# ProProject___2024-03-14.net
KiCad netlist of a schematic drawn in EasyEDA Pro
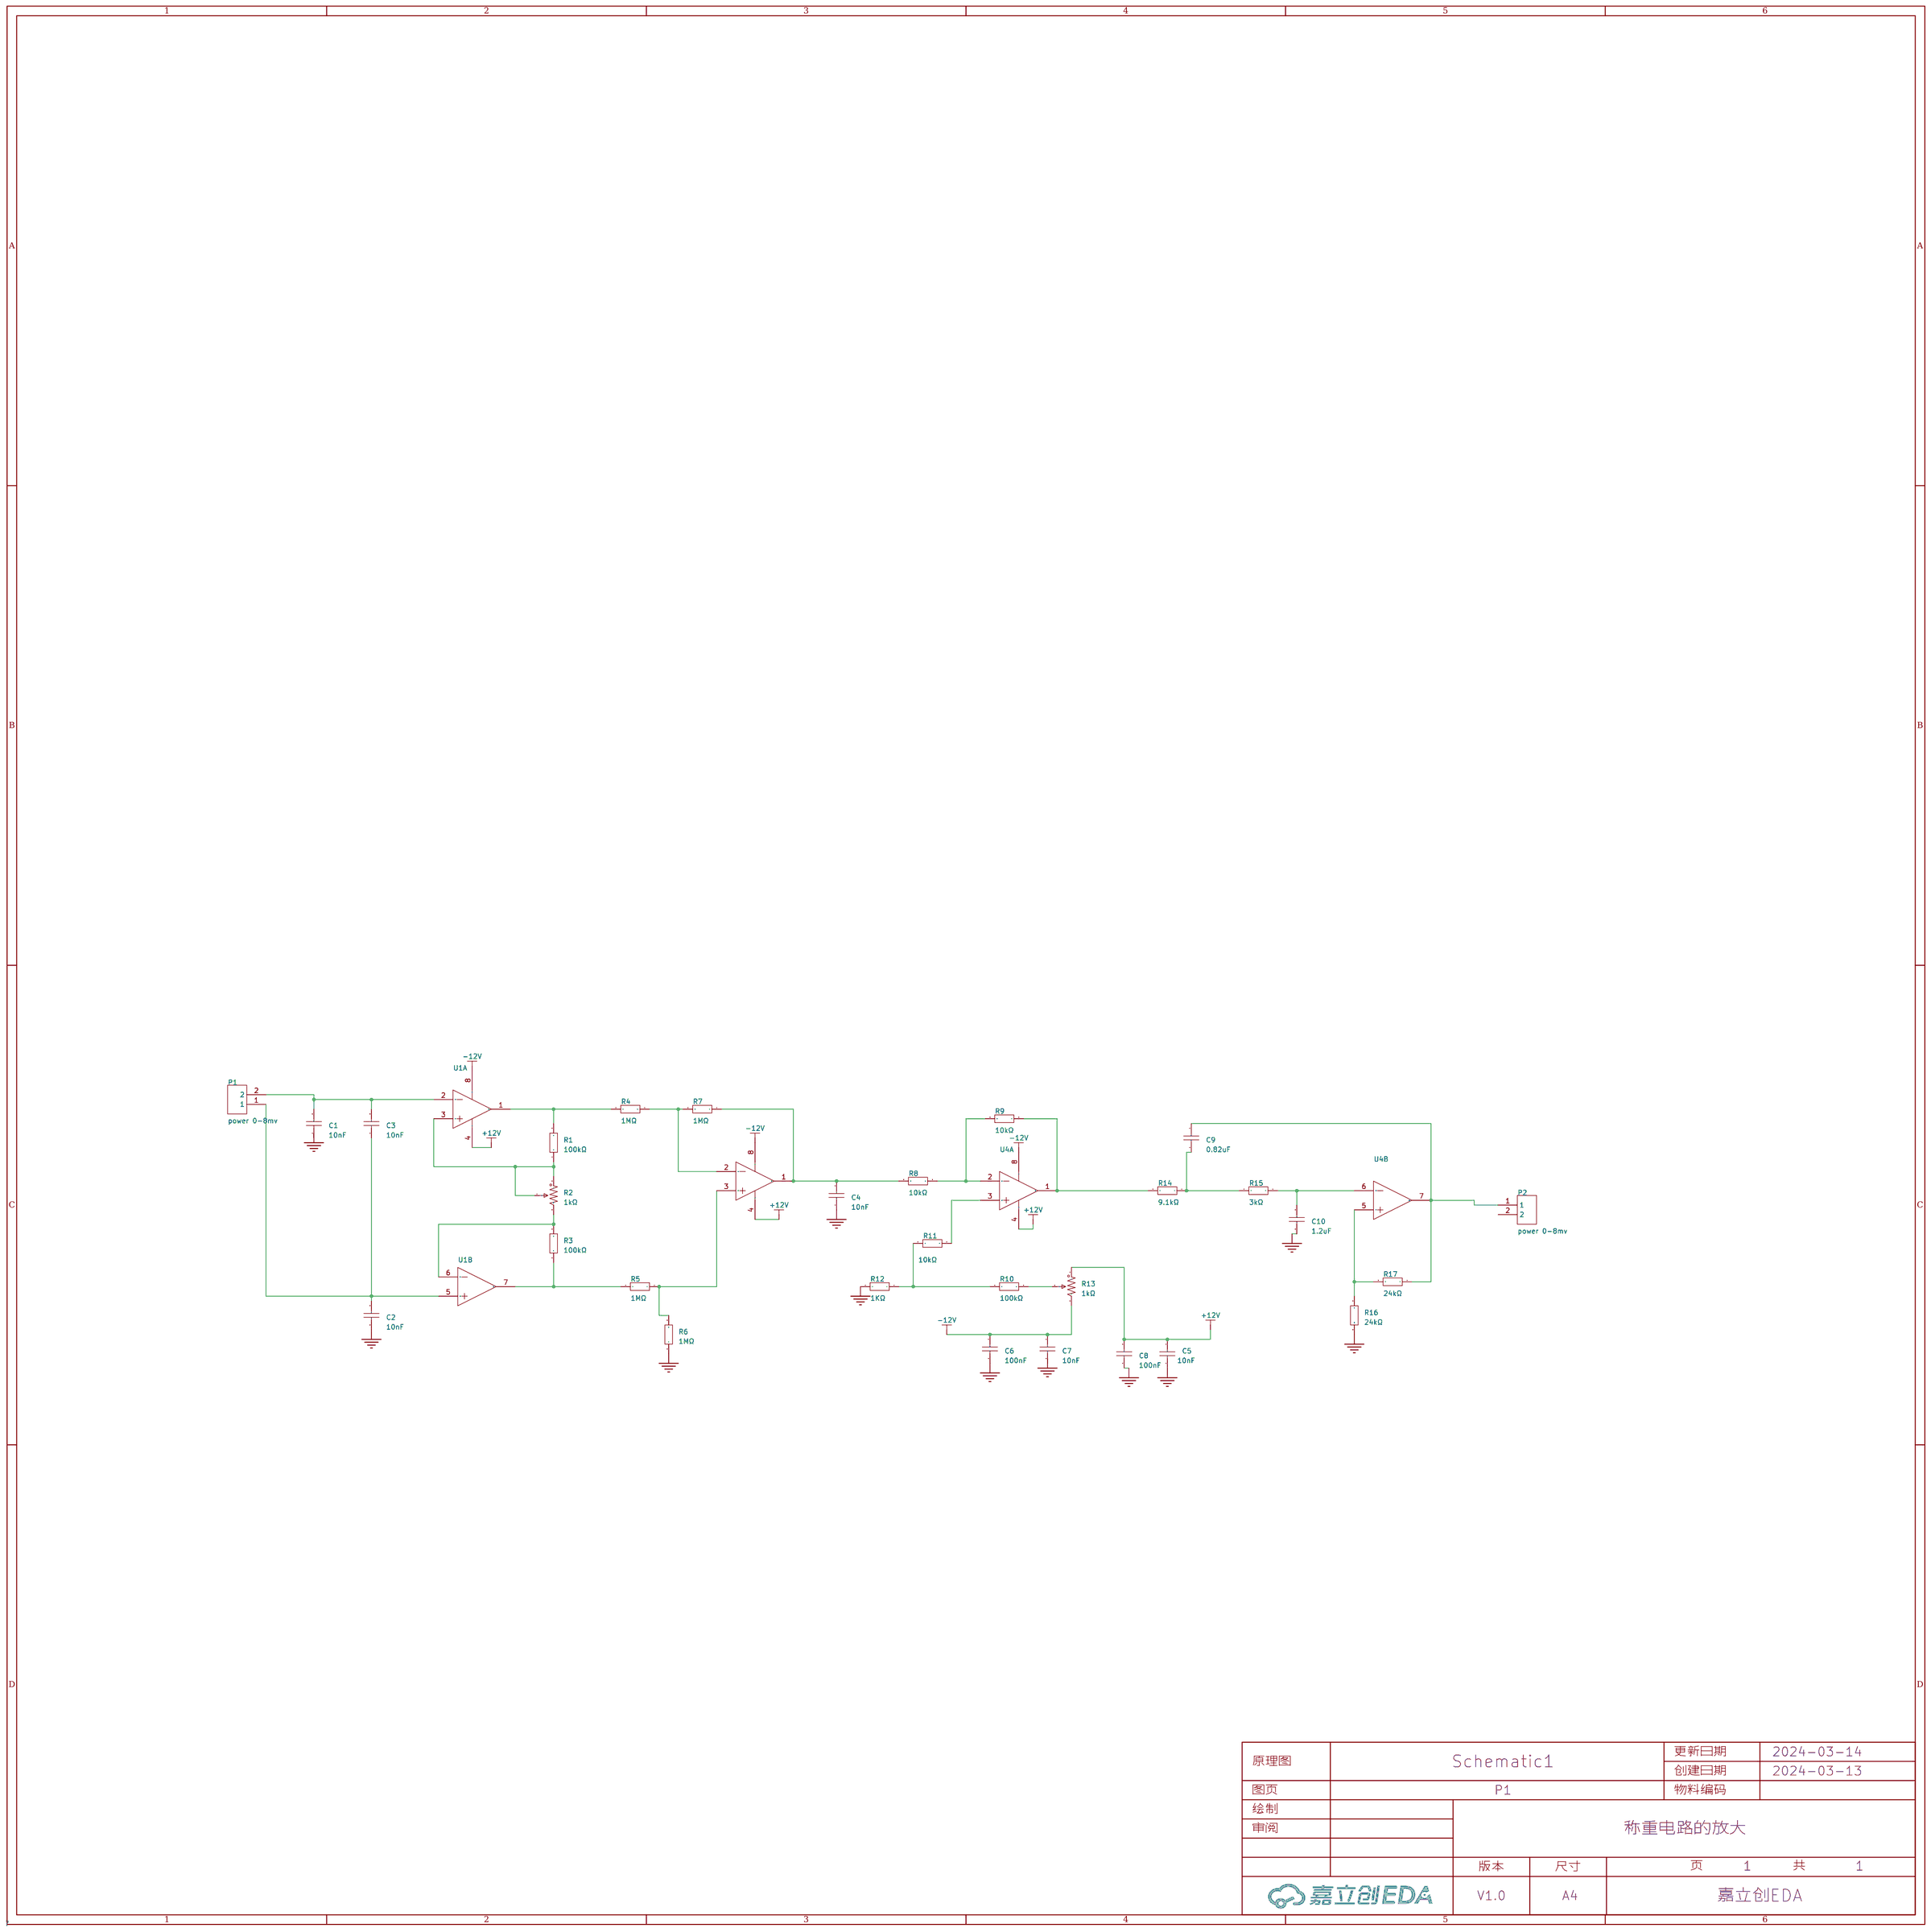
[diagram p0: schematic sheet]

(export (version "E")
  (design (tool "Eeschema 10.0.6"))
  (components
    (comp (ref "C1")
      (value "10nF")
      (footprint "easyedapro:C0603")
      (description "容值:100nF;精度:±10%;额定电压:50V;材质(温度系数):X7R;")
      (fields (field (name "Manufacturer Part") "0603B104K500NT") (field (name "Manufacturer") "FH(风华)"))
      (libsource (lib "easyedapro") (part "0603B104K500NT"))
    )
    (comp (ref "C2")
      (value "10nF")
      (footprint "easyedapro:C0603")
      (description "容值:100nF;精度:±10%;额定电压:50V;材质(温度系数):X7R;")
      (fields (field (name "Manufacturer Part") "0603B104K500NT") (field (name "Manufacturer") "FH(风华)"))
      (libsource (lib "easyedapro") (part "0603B104K500NT"))
    )
    (comp (ref "C3")
      (value "10nF")
      (footprint "easyedapro:C0603")
      (description "容值:100nF;精度:±10%;额定电压:50V;材质(温度系数):X7R;")
      (fields (field (name "Manufacturer Part") "0603B104K500NT") (field (name "Manufacturer") "FH(风华)"))
      (libsource (lib "easyedapro") (part "0603B104K500NT"))
    )
    (comp (ref "C4")
      (value "10nF")
      (footprint "easyedapro:C0603")
      (description "容值:100nF;精度:±10%;额定电压:50V;材质(温度系数):X7R;")
      (fields (field (name "Manufacturer Part") "0603B104K500NT") (field (name "Manufacturer") "FH(风华)"))
      (libsource (lib "easyedapro") (part "0603B104K500NT"))
    )
    (comp (ref "C5")
      (value "10nF")
      (footprint "easyedapro:C0603")
      (description "容值:100nF;精度:±10%;额定电压:50V;材质(温度系数):X7R;")
      (fields (field (name "Manufacturer Part") "0603B104K500NT") (field (name "Manufacturer") "FH(风华)"))
      (libsource (lib "easyedapro") (part "0603B104K500NT"))
    )
    (comp (ref "C6")
      (value "100nF")
      (footprint "easyedapro:C0603")
      (description "容值:100nF;精度:±10%;额定电压:50V;材质(温度系数):X7R;")
      (fields (field (name "Manufacturer Part") "0603B104K500NT") (field (name "Manufacturer") "FH(风华)"))
      (libsource (lib "easyedapro") (part "0603B104K500NT"))
    )
    (comp (ref "C7")
      (value "10nF")
      (footprint "easyedapro:C0603")
      (description "容值:100nF;精度:±10%;额定电压:50V;材质(温度系数):X7R;")
      (fields (field (name "Manufacturer Part") "0603B104K500NT") (field (name "Manufacturer") "FH(风华)"))
      (libsource (lib "easyedapro") (part "0603B104K500NT"))
    )
    (comp (ref "C8")
      (value "100nF")
      (footprint "easyedapro:C0603")
      (description "容值:100nF;精度:±10%;额定电压:50V;材质(温度系数):X7R;")
      (fields (field (name "Manufacturer Part") "0603B104K500NT") (field (name "Manufacturer") "FH(风华)"))
      (libsource (lib "easyedapro") (part "0603B104K500NT"))
    )
    (comp (ref "C9")
      (value "0.82uF")
      (footprint "easyedapro:C0603")
      (description "容值:100nF;精度:±10%;额定电压:50V;材质(温度系数):X7R;")
      (fields (field (name "Manufacturer Part") "0603B104K500NT") (field (name "Manufacturer") "FH(风华)"))
      (libsource (lib "easyedapro") (part "0603B104K500NT"))
    )
    (comp (ref "C10")
      (value "1.2uF")
      (footprint "easyedapro:C0603")
      (description "容值:100nF;精度:±10%;额定电压:50V;材质(温度系数):X7R;")
      (fields (field (name "Manufacturer Part") "0603B104K500NT") (field (name "Manufacturer") "FH(风华)"))
      (libsource (lib "easyedapro") (part "0603B104K500NT"))
    )
    (comp (ref "P1")
      (value "power 0-8mv")
      (footprint "easyedapro:CONN-TH_2P-P5.00_WJ500V-5.08-2P")
      (fields (field (name "Manufacturer") "KANGNEX(康奈克斯电气)"))
      (libsource (lib "easyedapro") (part "WJ500V-5.08-2P-14-00A"))
    )
    (comp (ref "P2")
      (value "power 0-8mv")
      (footprint "easyedapro:CONN-TH_2P-P5.00_WJ500V-5.08-2P")
      (fields (field (name "Manufacturer") "KANGNEX(康奈克斯电气)"))
      (libsource (lib "easyedapro") (part "WJ500V-5.08-2P-14-00A"))
    )
    (comp (ref "R1")
      (value "100kΩ")
      (footprint "easyedapro:R0603")
      (description "电阻类型:厚膜电阻;阻值:10kΩ;精度:±1%;功率:100mW;最大工作电压:75V;温度系数:±100ppm/°C;")
      (fields
        (field (name "Manufacturer Part") "0603WAF1002T5E")
        (field (name "Manufacturer") "UNI-ROYAL(厚声)")
      )
      (libsource (lib "easyedapro") (part "0603WAF1002T5E"))
    )
    (comp (ref "R2")
      (value "1kΩ")
      (footprint "easyedapro:RES-ADJ-TH_3362P")
      (description "阻值:10kΩ;精度:±10%;")
      (fields (field (name "Manufacturer Part") "3362P-1-103") (field (name "Manufacturer") "BOCHEN(博晨)"))
      (libsource (lib "easyedapro") (part "3362P-1-103_C118956"))
    )
    (comp (ref "R3")
      (value "100kΩ")
      (footprint "easyedapro:R0603")
      (description "电阻类型:厚膜电阻;阻值:10kΩ;精度:±1%;功率:100mW;最大工作电压:75V;温度系数:±100ppm/°C;")
      (fields
        (field (name "Manufacturer Part") "0603WAF1002T5E")
        (field (name "Manufacturer") "UNI-ROYAL(厚声)")
      )
      (libsource (lib "easyedapro") (part "0603WAF1002T5E"))
    )
    (comp (ref "R4")
      (value "1MΩ")
      (footprint "easyedapro:R0603")
      (description "电阻类型:厚膜电阻;阻值:10kΩ;精度:±1%;功率:100mW;最大工作电压:75V;温度系数:±100ppm/°C;")
      (fields
        (field (name "Manufacturer Part") "0603WAF1002T5E")
        (field (name "Manufacturer") "UNI-ROYAL(厚声)")
      )
      (libsource (lib "easyedapro") (part "0603WAF1002T5E"))
    )
    (comp (ref "R5")
      (value "1MΩ")
      (footprint "easyedapro:R0603")
      (description "电阻类型:厚膜电阻;阻值:10kΩ;精度:±1%;功率:100mW;最大工作电压:75V;温度系数:±100ppm/°C;")
      (fields
        (field (name "Manufacturer Part") "0603WAF1002T5E")
        (field (name "Manufacturer") "UNI-ROYAL(厚声)")
      )
      (libsource (lib "easyedapro") (part "0603WAF1002T5E"))
    )
    (comp (ref "R6")
      (value "1MΩ")
      (footprint "easyedapro:R0603")
      (description "电阻类型:厚膜电阻;阻值:10kΩ;精度:±1%;功率:100mW;最大工作电压:75V;温度系数:±100ppm/°C;")
      (fields
        (field (name "Manufacturer Part") "0603WAF1002T5E")
        (field (name "Manufacturer") "UNI-ROYAL(厚声)")
      )
      (libsource (lib "easyedapro") (part "0603WAF1002T5E"))
    )
    (comp (ref "R7")
      (value "1MΩ")
      (footprint "easyedapro:R0603")
      (description "电阻类型:厚膜电阻;阻值:10kΩ;精度:±1%;功率:100mW;最大工作电压:75V;温度系数:±100ppm/°C;")
      (fields
        (field (name "Manufacturer Part") "0603WAF1002T5E")
        (field (name "Manufacturer") "UNI-ROYAL(厚声)")
      )
      (libsource (lib "easyedapro") (part "0603WAF1002T5E"))
    )
    (comp (ref "R8")
      (value "10kΩ")
      (footprint "easyedapro:R0603")
      (description "电阻类型:厚膜电阻;阻值:10kΩ;精度:±1%;功率:100mW;最大工作电压:75V;温度系数:±100ppm/°C;")
      (fields
        (field (name "Manufacturer Part") "0603WAF1002T5E")
        (field (name "Manufacturer") "UNI-ROYAL(厚声)")
      )
      (libsource (lib "easyedapro") (part "0603WAF1002T5E"))
    )
    (comp (ref "R9")
      (value "10kΩ")
      (footprint "easyedapro:R0603")
      (description "电阻类型:厚膜电阻;阻值:10kΩ;精度:±1%;功率:100mW;最大工作电压:75V;温度系数:±100ppm/°C;")
      (fields
        (field (name "Manufacturer Part") "0603WAF1002T5E")
        (field (name "Manufacturer") "UNI-ROYAL(厚声)")
      )
      (libsource (lib "easyedapro") (part "0603WAF1002T5E"))
    )
    (comp (ref "R10")
      (value "100kΩ")
      (footprint "easyedapro:R0603")
      (description "电阻类型:厚膜电阻;阻值:10kΩ;精度:±1%;功率:100mW;最大工作电压:75V;温度系数:±100ppm/°C;")
      (fields
        (field (name "Manufacturer Part") "0603WAF1002T5E")
        (field (name "Manufacturer") "UNI-ROYAL(厚声)")
      )
      (libsource (lib "easyedapro") (part "0603WAF1002T5E"))
    )
    (comp (ref "R11")
      (value "10kΩ")
      (footprint "easyedapro:R0603")
      (description "电阻类型:厚膜电阻;阻值:10kΩ;精度:±1%;功率:100mW;最大工作电压:75V;温度系数:±100ppm/°C;")
      (fields
        (field (name "Manufacturer Part") "0603WAF1002T5E")
        (field (name "Manufacturer") "UNI-ROYAL(厚声)")
      )
      (libsource (lib "easyedapro") (part "0603WAF1002T5E"))
    )
    (comp (ref "R12")
      (value "1KΩ")
      (footprint "easyedapro:R0603")
      (description "电阻类型:厚膜电阻;阻值:10kΩ;精度:±1%;功率:100mW;最大工作电压:75V;温度系数:±100ppm/°C;")
      (fields
        (field (name "Manufacturer Part") "0603WAF1002T5E")
        (field (name "Manufacturer") "UNI-ROYAL(厚声)")
      )
      (libsource (lib "easyedapro") (part "0603WAF1002T5E"))
    )
    (comp (ref "R13")
      (value "1kΩ")
      (footprint "easyedapro:RES-ADJ-TH_3362P")
      (description "阻值:10kΩ;精度:±10%;")
      (fields (field (name "Manufacturer Part") "3362P-1-103") (field (name "Manufacturer") "BOCHEN(博晨)"))
      (libsource (lib "easyedapro") (part "3362P-1-103_C118956"))
    )
    (comp (ref "R14")
      (value "9.1kΩ")
      (footprint "easyedapro:R0603")
      (description "电阻类型:厚膜电阻;阻值:10kΩ;精度:±1%;功率:100mW;最大工作电压:75V;温度系数:±100ppm/°C;")
      (fields
        (field (name "Manufacturer Part") "0603WAF1002T5E")
        (field (name "Manufacturer") "UNI-ROYAL(厚声)")
      )
      (libsource (lib "easyedapro") (part "0603WAF1002T5E"))
    )
    (comp (ref "R15")
      (value "3kΩ")
      (footprint "easyedapro:R0603")
      (description "电阻类型:厚膜电阻;阻值:10kΩ;精度:±1%;功率:100mW;最大工作电压:75V;温度系数:±100ppm/°C;")
      (fields
        (field (name "Manufacturer Part") "0603WAF1002T5E")
        (field (name "Manufacturer") "UNI-ROYAL(厚声)")
      )
      (libsource (lib "easyedapro") (part "0603WAF1002T5E"))
    )
    (comp (ref "R16")
      (value "24kΩ")
      (footprint "easyedapro:R0603")
      (description "电阻类型:厚膜电阻;阻值:10kΩ;精度:±1%;功率:100mW;最大工作电压:75V;温度系数:±100ppm/°C;")
      (fields
        (field (name "Manufacturer Part") "0603WAF1002T5E")
        (field (name "Manufacturer") "UNI-ROYAL(厚声)")
      )
      (libsource (lib "easyedapro") (part "0603WAF1002T5E"))
    )
    (comp (ref "R17")
      (value "24kΩ")
      (footprint "easyedapro:R0603")
      (description "电阻类型:厚膜电阻;阻值:10kΩ;精度:±1%;功率:100mW;最大工作电压:75V;温度系数:±100ppm/°C;")
      (fields
        (field (name "Manufacturer Part") "0603WAF1002T5E")
        (field (name "Manufacturer") "UNI-ROYAL(厚声)")
      )
      (libsource (lib "easyedapro") (part "0603WAF1002T5E"))
    )
    (comp (ref "U1")
      (value "LM358N")
      (footprint "easyedapro:PDIP-8_L9.3-W6.4-P2.54-LS7.9-BL-1")
      (fields (field (name "Manufacturer") "XICOR"))
      (libsource (lib "easyedapro") (part "LM358N_C4366086"))
    )
    (comp (ref "U3")
      (value "LM358N")
      (footprint "easyedapro:PDIP-8_L9.3-W6.4-P2.54-LS7.9-BL-1")
      (fields (field (name "Manufacturer") "XICOR"))
      (libsource (lib "easyedapro") (part "LM358N_C4366086"))
    )
    (comp (ref "U4")
      (value "LM358N")
      (footprint "easyedapro:PDIP-8_L9.3-W6.4-P2.54-LS7.9-BL-1")
      (fields (field (name "Manufacturer") "XICOR"))
      (libsource (lib "easyedapro") (part "LM358N_C4366086"))
    )
  )
  (nets
    (net (code "1") (name "+12V") (class "Default")
      (node (ref "C5") (pin "2") (pinfunction "2_2") (pintype "input"))
      (node (ref "C8") (pin "2") (pinfunction "2_2") (pintype "input"))
      (node (ref "R13") (pin "1") (pinfunction "1_1") (pintype "input"))
      (node (ref "U1") (pin "4") (pinfunction "V-_4") (pintype "unspecified"))
      (node (ref "U3") (pin "4") (pinfunction "V-_4") (pintype "unspecified"))
      (node (ref "U4") (pin "4") (pinfunction "V-_4") (pintype "unspecified"))
    )
    (net (code "2") (name "-12V") (class "Default")
      (node (ref "C6") (pin "2") (pinfunction "2_2") (pintype "input"))
      (node (ref "C7") (pin "2") (pinfunction "2_2") (pintype "input"))
      (node (ref "R13") (pin "3") (pinfunction "3_3") (pintype "input"))
      (node (ref "U1") (pin "8") (pinfunction "V+_8") (pintype "unspecified"))
      (node (ref "U3") (pin "8") (pinfunction "V+_8") (pintype "unspecified"))
      (node (ref "U4") (pin "8") (pinfunction "V+_8") (pintype "unspecified"))
    )
    (net (code "3") (name "GND") (class "Default")
      (node (ref "C1") (pin "1") (pinfunction "1_1") (pintype "input"))
      (node (ref "C10") (pin "1") (pinfunction "1_1") (pintype "input"))
      (node (ref "C2") (pin "1") (pinfunction "1_1") (pintype "input"))
      (node (ref "C4") (pin "1") (pinfunction "1_1") (pintype "input"))
      (node (ref "C5") (pin "1") (pinfunction "1_1") (pintype "input"))
      (node (ref "C6") (pin "1") (pinfunction "1_1") (pintype "input"))
      (node (ref "C7") (pin "1") (pinfunction "1_1") (pintype "input"))
      (node (ref "C8") (pin "1") (pinfunction "1_1") (pintype "input"))
      (node (ref "R12") (pin "2") (pinfunction "2_2") (pintype "input"))
      (node (ref "R16") (pin "2") (pinfunction "2_2") (pintype "input"))
      (node (ref "R6") (pin "1") (pinfunction "1_1") (pintype "input"))
    )
    (net (code "4") (name "Net-(C9-Pad1)") (class "Default")
      (node (ref "C9") (pin "1") (pinfunction "1_1") (pintype "input"))
      (node (ref "R14") (pin "1") (pinfunction "1_1") (pintype "input"))
      (node (ref "R15") (pin "2") (pinfunction "2_2") (pintype "input"))
    )
    (net (code "5") (name "Net-(R10-Pad1)") (class "Default")
      (node (ref "R10") (pin "1") (pinfunction "1_1") (pintype "input"))
      (node (ref "R13") (pin "2") (pinfunction "2_2") (pintype "input"))
    )
    (net (code "6") (name "Net-(R10-Pad2)") (class "Default")
      (node (ref "R10") (pin "2") (pinfunction "2_2") (pintype "input"))
      (node (ref "R11") (pin "2") (pinfunction "2_2") (pintype "input"))
      (node (ref "R12") (pin "1") (pinfunction "1_1") (pintype "input"))
    )
    (net (code "7") (name "Net-(U1A-IN_A+)") (class "Default")
      (node (ref "R1") (pin "1") (pinfunction "1_1") (pintype "input"))
      (node (ref "R2") (pin "1") (pinfunction "1_1") (pintype "input"))
      (node (ref "R2") (pin "2") (pinfunction "2_2") (pintype "input"))
      (node (ref "U1") (pin "3") (pinfunction "IN_A+_3") (pintype "unspecified"))
    )
    (net (code "8") (name "Net-(U1A-IN_A-)") (class "Default")
      (node (ref "C1") (pin "2") (pinfunction "2_2") (pintype "input"))
      (node (ref "C3") (pin "2") (pinfunction "2_2") (pintype "input"))
      (node (ref "P1") (pin "2") (pinfunction "2_2") (pintype "unspecified"))
      (node (ref "U1") (pin "2") (pinfunction "IN_A-_2") (pintype "unspecified"))
    )
    (net (code "9") (name "Net-(U1A-OUT_A)") (class "Default")
      (node (ref "R1") (pin "2") (pinfunction "2_2") (pintype "input"))
      (node (ref "R4") (pin "2") (pinfunction "2_2") (pintype "input"))
      (node (ref "U1") (pin "1") (pinfunction "OUT_A_1") (pintype "output"))
    )
    (net (code "10") (name "Net-(U1B-IN_B+)") (class "Default")
      (node (ref "C2") (pin "2") (pinfunction "2_2") (pintype "input"))
      (node (ref "C3") (pin "1") (pinfunction "1_1") (pintype "input"))
      (node (ref "P1") (pin "1") (pinfunction "1_1") (pintype "unspecified"))
      (node (ref "U1") (pin "5") (pinfunction "IN_B+_5") (pintype "unspecified"))
    )
    (net (code "11") (name "Net-(U1B-IN_B-)") (class "Default")
      (node (ref "R2") (pin "3") (pinfunction "3_3") (pintype "input"))
      (node (ref "R3") (pin "2") (pinfunction "2_2") (pintype "input"))
      (node (ref "U1") (pin "6") (pinfunction "IN_B-_6") (pintype "unspecified"))
    )
    (net (code "12") (name "Net-(U1B-OUT_B)") (class "Default")
      (node (ref "R3") (pin "1") (pinfunction "1_1") (pintype "input"))
      (node (ref "R5") (pin "2") (pinfunction "2_2") (pintype "input"))
      (node (ref "U1") (pin "7") (pinfunction "OUT_B_7") (pintype "output"))
    )
    (net (code "13") (name "Net-(U3A-IN_A+)") (class "Default")
      (node (ref "R5") (pin "1") (pinfunction "1_1") (pintype "input"))
      (node (ref "R6") (pin "2") (pinfunction "2_2") (pintype "input"))
      (node (ref "U3") (pin "3") (pinfunction "IN_A+_3") (pintype "unspecified"))
    )
    (net (code "14") (name "Net-(U3A-IN_A-)") (class "Default")
      (node (ref "R4") (pin "1") (pinfunction "1_1") (pintype "input"))
      (node (ref "R7") (pin "2") (pinfunction "2_2") (pintype "input"))
      (node (ref "U3") (pin "2") (pinfunction "IN_A-_2") (pintype "unspecified"))
    )
    (net (code "15") (name "Net-(U3A-OUT_A)") (class "Default")
      (node (ref "C4") (pin "2") (pinfunction "2_2") (pintype "input"))
      (node (ref "R7") (pin "1") (pinfunction "1_1") (pintype "input"))
      (node (ref "R8") (pin "2") (pinfunction "2_2") (pintype "input"))
      (node (ref "U3") (pin "1") (pinfunction "OUT_A_1") (pintype "output"))
    )
    (net (code "16") (name "Net-(U4A-IN_A+)") (class "Default")
      (node (ref "R11") (pin "1") (pinfunction "1_1") (pintype "input"))
      (node (ref "U4") (pin "3") (pinfunction "IN_A+_3") (pintype "unspecified"))
    )
    (net (code "17") (name "Net-(U4A-IN_A-)") (class "Default")
      (node (ref "R8") (pin "1") (pinfunction "1_1") (pintype "input"))
      (node (ref "R9") (pin "2") (pinfunction "2_2") (pintype "input"))
      (node (ref "U4") (pin "2") (pinfunction "IN_A-_2") (pintype "unspecified"))
    )
    (net (code "18") (name "Net-(U4A-OUT_A)") (class "Default")
      (node (ref "R14") (pin "2") (pinfunction "2_2") (pintype "input"))
      (node (ref "R9") (pin "1") (pinfunction "1_1") (pintype "input"))
      (node (ref "U4") (pin "1") (pinfunction "OUT_A_1") (pintype "output"))
    )
    (net (code "19") (name "Net-(U4B-IN_B+)") (class "Default")
      (node (ref "R16") (pin "1") (pinfunction "1_1") (pintype "input"))
      (node (ref "R17") (pin "2") (pinfunction "2_2") (pintype "input"))
      (node (ref "U4") (pin "5") (pinfunction "IN_B+_5") (pintype "unspecified"))
    )
    (net (code "20") (name "Net-(U4B-IN_B-)") (class "Default")
      (node (ref "C10") (pin "2") (pinfunction "2_2") (pintype "input"))
      (node (ref "R15") (pin "1") (pinfunction "1_1") (pintype "input"))
      (node (ref "U4") (pin "6") (pinfunction "IN_B-_6") (pintype "unspecified"))
    )
    (net (code "21") (name "Net-(U4B-OUT_B)") (class "Default")
      (node (ref "C9") (pin "2") (pinfunction "2_2") (pintype "input"))
      (node (ref "P2") (pin "1") (pinfunction "1_1") (pintype "unspecified"))
      (node (ref "R17") (pin "1") (pinfunction "1_1") (pintype "input"))
      (node (ref "U4") (pin "7") (pinfunction "OUT_B_7") (pintype "output"))
    )
    (net (code "22") (name "unconnected-(P2-Pad2)") (class "Default")
      (node (ref "P2") (pin "2") (pinfunction "2_2") (pintype "unspecified"))
    )
  )
)
